# RL_2_Mini_V1_0_3.net
KiCad netlist of a schematic drawn in Altium Designer
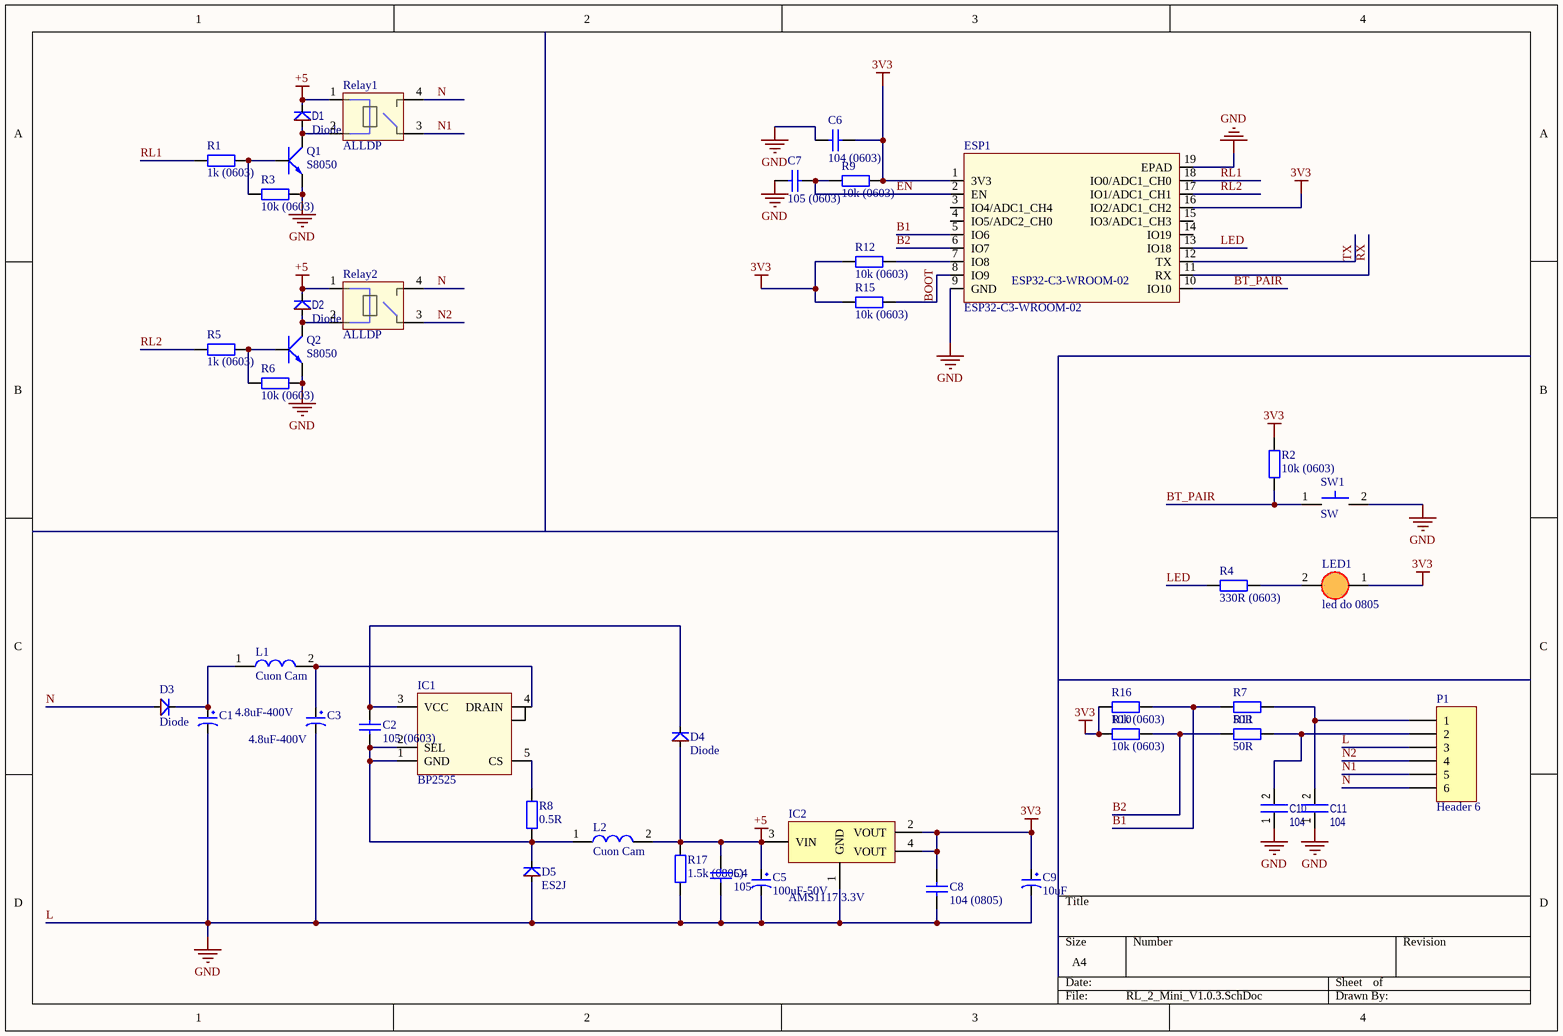
[diagram p0: RL_2_Mini_V1.0.3.SchDoc]

(export (version "E")
  (design (tool "Eeschema 10.0.6"))
  (components
    (comp (ref "C1")
      (value "4.8uF-400V")
      (footprint "tu hoa 8mm")
      (description "Cắm")
      (libsource (lib "THU VIEN SCH_21122018") (part "Tu Hoa 2.2uF 400V 8x12"))
    )
    (comp (ref "C2")
      (value "105 (0603)")
      (footprint "tu 0603")
      (description "Dán")
      (libsource (lib "THU VIEN SCH_21122018") (part "Tu 0603 105 16V 20%"))
    )
    (comp (ref "C3")
      (value "4.8uF-400V")
      (footprint "tu hoa 8mm")
      (description "Cắm")
      (libsource (lib "THU VIEN SCH_21122018") (part "Tu Hoa 2.2uF 400V 8x12"))
    )
    (comp (ref "C4")
      (value "105")
      (footprint "tu 0805")
      (description "Dán")
      (libsource (lib "THU VIEN SCH_21122018") (part "Tu 0805 104 50V 10%"))
    )
    (comp (ref "C5")
      (value "100uF-50V")
      (footprint "tu hoa 8mm")
      (description "Cắm")
      (libsource (lib "THU VIEN SCH_21122018") (part "Tu Hoa 100uF 50V 8x11"))
    )
    (comp (ref "C6")
      (value "104 (0603)")
      (footprint "tu 0603")
      (description "Dán")
      (libsource (lib "THU VIEN SCH_21122018") (part "Tu 0603 104 50V 10%"))
    )
    (comp (ref "C7")
      (value "105 (0603)")
      (footprint "tu 0603")
      (description "Dán")
      (libsource (lib "THU VIEN SCH_21122018") (part "Tu 0603 105 16V 20%"))
    )
    (comp (ref "C8")
      (value "104 (0805)")
      (footprint "tu 0805")
      (description "Dán")
      (libsource (lib "THU VIEN SCH_21122018") (part "Tu 0805 104 50V 10%"))
    )
    (comp (ref "C9")
      (value "10uF")
      (footprint "tu tantalum smd3216")
      (description "Dán")
      (libsource (lib "THU VIEN SCH_21122018") (part "Tu tantalum 10uF 16V SMD3216"))
    )
    (comp (ref "C10")
      (value "104")
      (footprint "CAP 0603")
      (description "Tu Ceramic")
      (libsource (lib "ToRa_E Lib by HauNe") (part "Tu Ceramic"))
    )
    (comp (ref "C11")
      (value "104")
      (footprint "CAP 0603")
      (description "Tu Ceramic")
      (libsource (lib "ToRa_E Lib by HauNe") (part "Tu Ceramic"))
    )
    (comp (ref "D1") (value "Diode") (footprint "SOD-123") (libsource (lib "ToRa_E Lib") (part "Diode")))
    (comp (ref "D2") (value "Diode") (footprint "SOD-123") (libsource (lib "ToRa_E Lib") (part "Diode")))
    (comp (ref "D3") (value "Diode") (footprint "SMA") (libsource (lib "") (part "Diode_1")))
    (comp (ref "D4") (value "Diode") (footprint "SMA") (libsource (lib "ToRa_E Lib by HauNe") (part "Diode")))
    (comp (ref "D5") (value "ES2J") (footprint "SMA") (libsource (lib "ToRa_E Lib by HauNe") (part "Diode")))
    (comp (ref "ESP1")
      (value "ESP32-C3-WROOM-02")
      (footprint "ESP32-C3-WROOM 02U")
      (libsource (lib "ToRa_E Lib by HauNe") (part "ESP32-C3-WROOM-02"))
    )
    (comp (ref "IC1")
      (value "BP2525")
      (footprint "SOT23-5")
      (libsource (lib "ToRa_E Lib by HauNe") (part "BP2525"))
    )
    (comp (ref "IC2")
      (value "AMS1117 3.3V")
      (footprint "SOT223")
      (description "Dán")
      (libsource (lib "THU VIEN SCH_21122018") (part "AMS1117 3.3V"))
    )
    (comp (ref "L1")
      (value "Cuon Cam")
      (footprint "0510 - H")
      (libsource (lib "ToRa_E Lib by HauNe") (part "Cuon Cam"))
    )
    (comp (ref "L2")
      (value "Cuon Cam")
      (footprint "PRS8040 - HALF")
      (libsource (lib "ToRa_E Lib by HauNe") (part "Cuon Cam"))
    )
    (comp (ref "LED1")
      (value "led do 0805")
      (footprint "led 0805")
      (description "Dán")
      (libsource (lib "THU VIEN SCH_21122018") (part "Led 0805 Do"))
    )
    (comp (ref "P1")
      (value "Header 6")
      (footprint "KF127-3P")
      (description "Header, 6-Pin")
      (fields (field (name "PUBLISHER") "Altium Limited"))
      (libsource (lib "2_sw") (part "Header 6"))
    )
    (comp (ref "Q1")
      (value "S8050")
      (footprint "SOT23B")
      (description "Dán")
      (libsource (lib "THU VIEN SCH_21122018") (part "S8050"))
    )
    (comp (ref "Q2")
      (value "S8050")
      (footprint "SOT23B")
      (description "Dán")
      (libsource (lib "THU VIEN SCH_21122018") (part "S8050"))
    )
    (comp (ref "R1")
      (value "1k (0603)")
      (footprint "tro 0603")
      (description "Dán")
      (libsource (lib "THU VIEN SCH_21122018") (part "Tro 0603 5% 1k"))
    )
    (comp (ref "R2")
      (value "10k (0603)")
      (footprint "tro 0603")
      (description "Dán")
      (libsource (lib "THU VIEN SCH_21122018") (part "Tro 0603 5% 10k"))
    )
    (comp (ref "R3")
      (value "10k (0603)")
      (footprint "tro 0603")
      (description "Dán")
      (libsource (lib "THU VIEN SCH_21122018") (part "Tro 0603 5% 10k"))
    )
    (comp (ref "R4")
      (value "330R (0603)")
      (footprint "tro 0603")
      (description "Dán")
      (libsource (lib "THU VIEN SCH_21122018") (part "Tro 0603 5% 330R"))
    )
    (comp (ref "R5")
      (value "1k (0603)")
      (footprint "tro 0603")
      (description "Dán")
      (libsource (lib "THU VIEN SCH_21122018") (part "Tro 0603 5% 1k"))
    )
    (comp (ref "R6")
      (value "10k (0603)")
      (footprint "tro 0603")
      (description "Dán")
      (libsource (lib "THU VIEN SCH_21122018") (part "Tro 0603 5% 10k"))
    )
    (comp (ref "R7")
      (value "50R")
      (footprint "tro 0603")
      (description "Dán")
      (libsource (lib "THU VIEN SCH_21122018") (part "Tro 0603 5% 10k"))
    )
    (comp (ref "R8")
      (value "0.5R")
      (footprint "TRO 1206")
      (description "Dán")
      (libsource (lib "THU VIEN SCH_21122018") (part "Tro 1206 5% 0R"))
    )
    (comp (ref "R9")
      (value "10k (0603)")
      (footprint "tro 0603")
      (description "Dán")
      (libsource (lib "THU VIEN SCH_21122018") (part "Tro 0603 5% 10k"))
    )
    (comp (ref "R10")
      (value "10k (0603)")
      (footprint "tro 0603")
      (description "Dán")
      (libsource (lib "THU VIEN SCH_21122018") (part "Tro 0603 5% 10k"))
    )
    (comp (ref "R11")
      (value "50R")
      (footprint "tro 0603")
      (description "Dán")
      (libsource (lib "THU VIEN SCH_21122018") (part "Tro 0603 5% 10k"))
    )
    (comp (ref "R12")
      (value "10k (0603)")
      (footprint "tro 0603")
      (description "Dán")
      (libsource (lib "THU VIEN SCH_21122018") (part "Tro 0603 5% 10k"))
    )
    (comp (ref "R15")
      (value "10k (0603)")
      (footprint "tro 0603")
      (description "Dán")
      (libsource (lib "THU VIEN SCH_21122018") (part "Tro 0603 5% 10k"))
    )
    (comp (ref "R16")
      (value "10k (0603)")
      (footprint "tro 0603")
      (description "Dán")
      (libsource (lib "THU VIEN SCH_21122018") (part "Tro 0603 5% 10k"))
    )
    (comp (ref "R17")
      (value "1.5k (0805)")
      (footprint "tro 0805")
      (description "Dán")
      (libsource (lib "THU VIEN SCH_21122018") (part "Tro 0805 5% 1.5k"))
    )
    (comp (ref "Relay1")
      (value "ALLDP")
      (footprint "H32F")
      (libsource (lib "ToRa_E Lib by HauNe") (part "Relay 4 Chan"))
    )
    (comp (ref "Relay2")
      (value "ALLDP")
      (footprint "H32F")
      (libsource (lib "ToRa_E Lib by HauNe") (part "Relay 4 Chan"))
    )
    (comp (ref "SW1")
      (value "SW")
      (footprint "SW 3x4mm SMD")
      (libsource (lib "ToRa_E Lib by HauNe") (part "Nut Nhan 2 chan"))
    )
  )
  (nets
    (net (code "1") (name "+5") (class "Default")
      (node (ref "C4") (pin "1") (pinfunction "1_1") (pintype "passive"))
      (node (ref "C5") (pin "1") (pinfunction "1_1") (pintype "passive"))
      (node (ref "D1") (pin "2") (pinfunction "K_2") (pintype "passive"))
      (node (ref "D2") (pin "2") (pinfunction "K_2") (pintype "passive"))
      (node (ref "D4") (pin "1") (pinfunction "A_1") (pintype "passive"))
      (node (ref "IC2") (pin "3") (pinfunction "VIN_3") (pintype "passive"))
      (node (ref "L2") (pin "2") (pinfunction "2_2") (pintype "passive"))
      (node (ref "R17") (pin "2") (pinfunction "2_2") (pintype "passive"))
      (node (ref "Relay1") (pin "1") (pinfunction "1_1") (pintype "passive"))
      (node (ref "Relay2") (pin "1") (pinfunction "1_1") (pintype "passive"))
    )
    (net (code "2") (name "/B1") (class "Default")
      (node (ref "ESP1") (pin "5") (pinfunction "IO6_5") (pintype "passive"))
      (node (ref "R16") (pin "2") (pinfunction "2_2") (pintype "passive"))
      (node (ref "R7") (pin "1") (pinfunction "1_1") (pintype "passive"))
    )
    (net (code "3") (name "/B2") (class "Default")
      (node (ref "ESP1") (pin "6") (pinfunction "IO7_6") (pintype "passive"))
      (node (ref "R10") (pin "2") (pinfunction "2_2") (pintype "passive"))
      (node (ref "R11") (pin "1") (pinfunction "1_1") (pintype "passive"))
    )
    (net (code "4") (name "/BOOT") (class "Default")
      (node (ref "ESP1") (pin "8") (pinfunction "IO9_8") (pintype "passive"))
      (node (ref "R15") (pin "2") (pinfunction "2_2") (pintype "passive"))
    )
    (net (code "5") (name "/BT_PAIR") (class "Default")
      (node (ref "ESP1") (pin "10") (pinfunction "IO10_10") (pintype "passive"))
      (node (ref "R2") (pin "1") (pinfunction "1_1") (pintype "passive"))
      (node (ref "SW1") (pin "1") (pinfunction "1_1") (pintype "passive"))
    )
    (net (code "6") (name "/EN") (class "Default")
      (node (ref "C7") (pin "1") (pinfunction "1_1") (pintype "passive"))
      (node (ref "ESP1") (pin "2") (pinfunction "EN_2") (pintype "passive"))
      (node (ref "R9") (pin "1") (pinfunction "1_1") (pintype "passive"))
    )
    (net (code "7") (name "/LED") (class "Default")
      (node (ref "ESP1") (pin "13") (pinfunction "IO18_13") (pintype "passive"))
      (node (ref "R4") (pin "1") (pinfunction "1_1") (pintype "passive"))
    )
    (net (code "8") (name "/N") (class "Default")
      (node (ref "D3") (pin "1") (pinfunction "A_1") (pintype "passive"))
      (node (ref "P1") (pin "6") (pinfunction "6_6") (pintype "passive"))
      (node (ref "Relay1") (pin "4") (pinfunction "4_4") (pintype "passive"))
      (node (ref "Relay2") (pin "4") (pinfunction "4_4") (pintype "passive"))
    )
    (net (code "9") (name "/N1") (class "Default")
      (node (ref "P1") (pin "5") (pinfunction "5_5") (pintype "passive"))
      (node (ref "Relay1") (pin "3") (pinfunction "3_3") (pintype "passive"))
    )
    (net (code "10") (name "/N2") (class "Default")
      (node (ref "P1") (pin "4") (pinfunction "4_4") (pintype "passive"))
      (node (ref "Relay2") (pin "3") (pinfunction "3_3") (pintype "passive"))
    )
    (net (code "11") (name "/RL1") (class "Default")
      (node (ref "ESP1") (pin "18") (pinfunction "IO0/ADC1_CH0_18") (pintype "passive"))
      (node (ref "R1") (pin "1") (pinfunction "1_1") (pintype "passive"))
    )
    (net (code "12") (name "/RL2") (class "Default")
      (node (ref "ESP1") (pin "17") (pinfunction "IO1/ADC1_CH1_17") (pintype "passive"))
      (node (ref "R5") (pin "1") (pinfunction "1_1") (pintype "passive"))
    )
    (net (code "13") (name "/RX") (class "Default")
      (node (ref "ESP1") (pin "11") (pinfunction "RX_11") (pintype "passive"))
    )
    (net (code "14") (name "/TX") (class "Default")
      (node (ref "ESP1") (pin "12") (pinfunction "TX_12") (pintype "passive"))
    )
    (net (code "15") (name "3V3") (class "Default")
      (node (ref "C6") (pin "1") (pinfunction "1_1") (pintype "passive"))
      (node (ref "C8") (pin "1") (pinfunction "1_1") (pintype "passive"))
      (node (ref "C9") (pin "1") (pinfunction "1_1") (pintype "passive"))
      (node (ref "ESP1") (pin "1") (pinfunction "3V3_1") (pintype "passive"))
      (node (ref "ESP1") (pin "16") (pinfunction "IO2/ADC1_CH2_16") (pintype "passive"))
      (node (ref "IC2") (pin "2") (pinfunction "VOUT_2") (pintype "passive"))
      (node (ref "IC2") (pin "4") (pinfunction "VOUT_4") (pintype "passive"))
      (node (ref "LED1") (pin "1") (pinfunction "A_1") (pintype "passive"))
      (node (ref "R10") (pin "1") (pinfunction "1_1") (pintype "passive"))
      (node (ref "R12") (pin "1") (pinfunction "1_1") (pintype "passive"))
      (node (ref "R15") (pin "1") (pinfunction "1_1") (pintype "passive"))
      (node (ref "R16") (pin "1") (pinfunction "1_1") (pintype "passive"))
      (node (ref "R2") (pin "2") (pinfunction "2_2") (pintype "passive"))
      (node (ref "R9") (pin "2") (pinfunction "2_2") (pintype "passive"))
    )
    (net (code "16") (name "GND") (class "Default")
      (node (ref "C1") (pin "2") (pinfunction "2_2") (pintype "passive"))
      (node (ref "C10") (pin "1") (pinfunction "1_1") (pintype "passive"))
      (node (ref "C11") (pin "1") (pinfunction "1_1") (pintype "passive"))
      (node (ref "C3") (pin "2") (pinfunction "2_2") (pintype "passive"))
      (node (ref "C4") (pin "2") (pinfunction "2_2") (pintype "passive"))
      (node (ref "C5") (pin "2") (pinfunction "2_2") (pintype "passive"))
      (node (ref "C6") (pin "2") (pinfunction "2_2") (pintype "passive"))
      (node (ref "C7") (pin "2") (pinfunction "2_2") (pintype "passive"))
      (node (ref "C8") (pin "2") (pinfunction "2_2") (pintype "passive"))
      (node (ref "C9") (pin "2") (pinfunction "2_2") (pintype "passive"))
      (node (ref "D5") (pin "1") (pinfunction "A_1") (pintype "passive"))
      (node (ref "ESP1") (pin "19") (pinfunction "EPAD_19") (pintype "passive"))
      (node (ref "ESP1") (pin "9") (pinfunction "GND_9") (pintype "passive"))
      (node (ref "IC2") (pin "1") (pinfunction "GND_1") (pintype "passive"))
      (node (ref "P1") (pin "3") (pinfunction "3_3") (pintype "passive"))
      (node (ref "Q1") (pin "2") (pinfunction "E_2") (pintype "passive"))
      (node (ref "Q2") (pin "2") (pinfunction "E_2") (pintype "passive"))
      (node (ref "R17") (pin "1") (pinfunction "1_1") (pintype "passive"))
      (node (ref "R3") (pin "2") (pinfunction "2_2") (pintype "passive"))
      (node (ref "R6") (pin "2") (pinfunction "2_2") (pintype "passive"))
      (node (ref "SW1") (pin "2") (pinfunction "2_2") (pintype "passive"))
    )
    (net (code "17") (name "Net-(C10-Pad2)") (class "Default")
      (node (ref "C10") (pin "2") (pinfunction "2_2") (pintype "passive"))
      (node (ref "P1") (pin "2") (pinfunction "2_2") (pintype "passive"))
      (node (ref "R11") (pin "2") (pinfunction "2_2") (pintype "passive"))
    )
    (net (code "18") (name "Net-(C11-Pad2)") (class "Default")
      (node (ref "C11") (pin "2") (pinfunction "2_2") (pintype "passive"))
      (node (ref "P1") (pin "1") (pinfunction "1_1") (pintype "passive"))
      (node (ref "R7") (pin "2") (pinfunction "2_2") (pintype "passive"))
    )
    (net (code "19") (name "Net-(D1-A)") (class "Default")
      (node (ref "D1") (pin "1") (pinfunction "A_1") (pintype "passive"))
      (node (ref "Q1") (pin "3") (pinfunction "C_3") (pintype "passive"))
      (node (ref "Relay1") (pin "2") (pinfunction "2_2") (pintype "passive"))
    )
    (net (code "20") (name "Net-(D2-A)") (class "Default")
      (node (ref "D2") (pin "1") (pinfunction "A_1") (pintype "passive"))
      (node (ref "Q2") (pin "3") (pinfunction "C_3") (pintype "passive"))
      (node (ref "Relay2") (pin "2") (pinfunction "2_2") (pintype "passive"))
    )
    (net (code "21") (name "Net-(D3-K)") (class "Default")
      (node (ref "C1") (pin "1") (pinfunction "1_1") (pintype "passive"))
      (node (ref "D3") (pin "2") (pinfunction "K_2") (pintype "passive"))
      (node (ref "L1") (pin "1") (pinfunction "1_1") (pintype "passive"))
    )
    (net (code "22") (name "Net-(D4-K)") (class "Default")
      (node (ref "C2") (pin "1") (pinfunction "1_1") (pintype "passive"))
      (node (ref "D4") (pin "2") (pinfunction "K_2") (pintype "passive"))
      (node (ref "IC1") (pin "3") (pinfunction "VCC_3") (pintype "passive"))
    )
    (net (code "23") (name "Net-(D5-K)") (class "Default")
      (node (ref "C2") (pin "2") (pinfunction "2_2") (pintype "passive"))
      (node (ref "D5") (pin "2") (pinfunction "K_2") (pintype "passive"))
      (node (ref "IC1") (pin "1") (pinfunction "GND_1") (pintype "passive"))
      (node (ref "IC1") (pin "2") (pinfunction "SEL_2") (pintype "passive"))
      (node (ref "L2") (pin "1") (pinfunction "1_1") (pintype "passive"))
      (node (ref "R8") (pin "1") (pinfunction "1_1") (pintype "passive"))
    )
    (net (code "24") (name "Net-(ESP1-IO8)") (class "Default")
      (node (ref "ESP1") (pin "7") (pinfunction "IO8_7") (pintype "passive"))
      (node (ref "R12") (pin "2") (pinfunction "2_2") (pintype "passive"))
    )
    (net (code "25") (name "Net-(IC1-CS)") (class "Default")
      (node (ref "IC1") (pin "5") (pinfunction "CS_5") (pintype "passive"))
      (node (ref "R8") (pin "2") (pinfunction "2_2") (pintype "passive"))
    )
    (net (code "26") (name "Net-(IC1-DRAIN)") (class "Default")
      (node (ref "C3") (pin "1") (pinfunction "1_1") (pintype "passive"))
      (node (ref "IC1") (pin "4") (pinfunction "DRAIN_4") (pintype "passive"))
      (node (ref "L1") (pin "2") (pinfunction "2_2") (pintype "passive"))
    )
    (net (code "27") (name "Net-(LED1-K)") (class "Default")
      (node (ref "LED1") (pin "2") (pinfunction "K_2") (pintype "passive"))
      (node (ref "R4") (pin "2") (pinfunction "2_2") (pintype "passive"))
    )
    (net (code "28") (name "Net-(Q1-B)") (class "Default")
      (node (ref "Q1") (pin "1") (pinfunction "B_1") (pintype "passive"))
      (node (ref "R1") (pin "2") (pinfunction "2_2") (pintype "passive"))
      (node (ref "R3") (pin "1") (pinfunction "1_1") (pintype "passive"))
    )
    (net (code "29") (name "Net-(Q2-B)") (class "Default")
      (node (ref "Q2") (pin "1") (pinfunction "B_1") (pintype "passive"))
      (node (ref "R5") (pin "2") (pinfunction "2_2") (pintype "passive"))
      (node (ref "R6") (pin "1") (pinfunction "1_1") (pintype "passive"))
    )
    (net (code "30") (name "unconnected-(ESP1-IO3{slash}ADC1_CH3-Pad15)") (class "Default")
      (node (ref "ESP1") (pin "15") (pinfunction "IO3/ADC1_CH3_15") (pintype "passive"))
    )
    (net (code "31") (name "unconnected-(ESP1-IO4{slash}ADC1_CH4-Pad3)") (class "Default")
      (node (ref "ESP1") (pin "3") (pinfunction "IO4/ADC1_CH4_3") (pintype "passive"))
    )
    (net (code "32") (name "unconnected-(ESP1-IO5{slash}ADC2_CH0-Pad4)") (class "Default")
      (node (ref "ESP1") (pin "4") (pinfunction "IO5/ADC2_CH0_4") (pintype "passive"))
    )
    (net (code "33") (name "unconnected-(ESP1-IO19-Pad14)") (class "Default")
      (node (ref "ESP1") (pin "14") (pinfunction "IO19_14") (pintype "passive"))
    )
  )
)
